# backscatter_power_module_v1_1.net
KiCad netlist of a schematic drawn in EAGLE
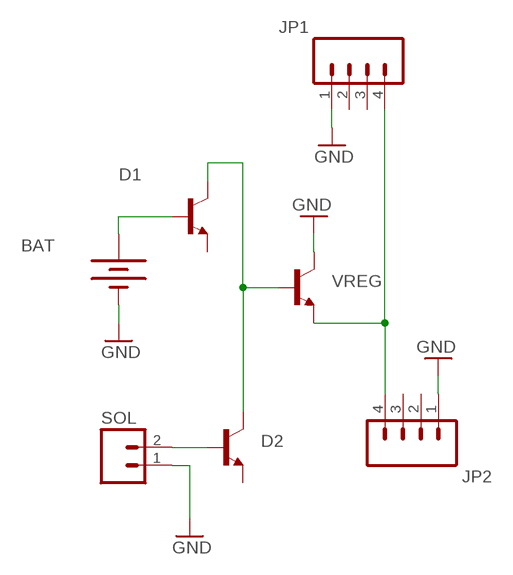
[diagram p0: schematic, sheet 1]

(export (version "E")
  (design (tool "Eeschema 10.0.6"))
  (components
    (comp (ref "BAT")
      (value "BATTERY20PTH_LAB")
      (footprint "eagle-import:BATTCOM_20MM_PTH")
      (libsource (lib "eagle-import") (part "BATTERY20PTH_LAB"))
    )
    (comp (ref "D1")
      (value "TRANSISTOR_NPNSOT23")
      (footprint "eagle-import:SOT23")
      (libsource (lib "eagle-import") (part "TRANSISTOR_NPNSOT23"))
    )
    (comp (ref "D2")
      (value "TRANSISTOR_NPNSOT23")
      (footprint "eagle-import:SOT23")
      (libsource (lib "eagle-import") (part "TRANSISTOR_NPNSOT23"))
    )
    (comp (ref "JP1")
      (value "M04LOCK")
      (footprint "eagle-import:1X04_LOCK")
      (libsource (lib "eagle-import") (part "M04LOCK"))
    )
    (comp (ref "JP2")
      (value "M04LOCK")
      (footprint "eagle-import:1X04_LOCK")
      (libsource (lib "eagle-import") (part "M04LOCK"))
    )
    (comp (ref "SOL")
      (value "M02LOCK")
      (footprint "eagle-import:1X02_LOCK")
      (libsource (lib "eagle-import") (part "M02LOCK"))
    )
    (comp (ref "VREG")
      (value "TRANSISTOR_NPNSOT23")
      (footprint "eagle-import:SOT23")
      (libsource (lib "eagle-import") (part "TRANSISTOR_NPNSOT23"))
    )
  )
  (nets
    (net (code "1") (name "GND") (class "Default")
      (node (ref "BAT") (pin "2") (pinfunction "-_2") (pintype "power_in"))
      (node (ref "JP1") (pin "1") (pinfunction "1_1") (pintype "passive"))
      (node (ref "JP2") (pin "1") (pinfunction "1_1") (pintype "passive"))
      (node (ref "SOL") (pin "1") (pinfunction "1_1") (pintype "passive"))
      (node (ref "VREG") (pin "3") (pinfunction "C_3") (pintype "passive"))
    )
    (net (code "2") (name "Net-(BAT-+)") (class "Default")
      (node (ref "BAT") (pin "1") (pinfunction "+_1") (pintype "power_in"))
      (node (ref "D1") (pin "1") (pinfunction "B_1") (pintype "passive"))
    )
    (net (code "3") (name "Net-(D1-C)") (class "Default")
      (node (ref "D1") (pin "3") (pinfunction "C_3") (pintype "passive"))
      (node (ref "D2") (pin "3") (pinfunction "C_3") (pintype "passive"))
      (node (ref "VREG") (pin "1") (pinfunction "B_1") (pintype "passive"))
    )
    (net (code "4") (name "Net-(D2-B)") (class "Default")
      (node (ref "D2") (pin "1") (pinfunction "B_1") (pintype "passive"))
      (node (ref "SOL") (pin "2") (pinfunction "2_2") (pintype "passive"))
    )
    (net (code "5") (name "Net-(VREG-E)") (class "Default")
      (node (ref "JP1") (pin "4") (pinfunction "4_4") (pintype "passive"))
      (node (ref "JP2") (pin "4") (pinfunction "4_4") (pintype "passive"))
      (node (ref "VREG") (pin "2") (pinfunction "E_2") (pintype "passive"))
    )
    (net (code "6") (name "unconnected-(D1-E-Pad2)") (class "Default")
      (node (ref "D1") (pin "2") (pinfunction "E_2") (pintype "passive"))
    )
    (net (code "7") (name "unconnected-(D2-E-Pad2)") (class "Default")
      (node (ref "D2") (pin "2") (pinfunction "E_2") (pintype "passive"))
    )
    (net (code "8") (name "unconnected-(JP1-Pad2)") (class "Default")
      (node (ref "JP1") (pin "2") (pinfunction "2_2") (pintype "passive"))
    )
    (net (code "9") (name "unconnected-(JP1-Pad3)") (class "Default")
      (node (ref "JP1") (pin "3") (pinfunction "3_3") (pintype "passive"))
    )
    (net (code "10") (name "unconnected-(JP2-Pad2)") (class "Default")
      (node (ref "JP2") (pin "2") (pinfunction "2_2") (pintype "passive"))
    )
    (net (code "11") (name "unconnected-(JP2-Pad3)") (class "Default")
      (node (ref "JP2") (pin "3") (pinfunction "3_3") (pintype "passive"))
    )
  )
)
